# 2_pow_input.net
KiCad netlist of a schematic drawn in EAGLE
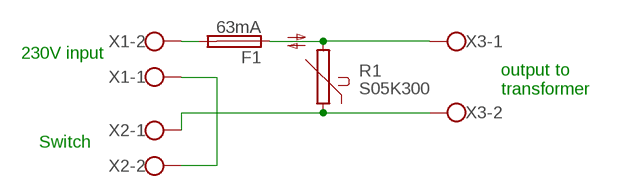
[diagram p0: schematic, sheet 1]

(export (version "E")
  (design (tool "Eeschema 10.0.6"))
  (components
    (comp (ref "F1")
      (value "63mA")
      (footprint "eagle-import:SH22,5A")
      (libsource (lib "eagle-import") (part "SH22,5A"))
    )
    (comp (ref "R1")
      (value "S05K300")
      (footprint "eagle-import:S05K300")
      (libsource (lib "eagle-import") (part "S05K300"))
    )
    (comp (ref "X1")
      (value "W237-02P")
      (footprint "eagle-import:W237-132")
      (libsource (lib "eagle-import") (part "W237-02P"))
    )
    (comp (ref "X2")
      (value "W237-02P")
      (footprint "eagle-import:W237-132")
      (libsource (lib "eagle-import") (part "W237-02P"))
    )
    (comp (ref "X3")
      (value "W237-02P")
      (footprint "eagle-import:W237-132")
      (libsource (lib "eagle-import") (part "W237-02P"))
    )
  )
  (nets
    (net (code "1") (name "Net-(X1A-KL)") (class "Default")
      (node (ref "X1") (pin "1") (pinfunction "KL_1") (pintype "passive"))
      (node (ref "X2") (pin "2") (pinfunction "KL_2") (pintype "passive"))
    )
    (net (code "2") (name "Net-(X1B-KL)") (class "Default")
      (node (ref "F1") (pin "2") (pinfunction "2_2") (pintype "passive"))
      (node (ref "X1") (pin "2") (pinfunction "KL_2") (pintype "passive"))
    )
    (net (code "3") (name "Net-(X2A-KL)") (class "Default")
      (node (ref "R1") (pin "1") (pinfunction "1_1") (pintype "passive"))
      (node (ref "X2") (pin "1") (pinfunction "KL_1") (pintype "passive"))
      (node (ref "X3") (pin "2") (pinfunction "KL_2") (pintype "passive"))
    )
    (net (code "4") (name "Net-(X3A-KL)") (class "Default")
      (node (ref "F1") (pin "1") (pinfunction "1_1") (pintype "passive"))
      (node (ref "R1") (pin "2") (pinfunction "2_2") (pintype "passive"))
      (node (ref "X3") (pin "1") (pinfunction "KL_1") (pintype "passive"))
    )
  )
)
